# P09_DRV2605L_Motor_Driver.net
KiCad netlist of a schematic drawn in Altium Designer
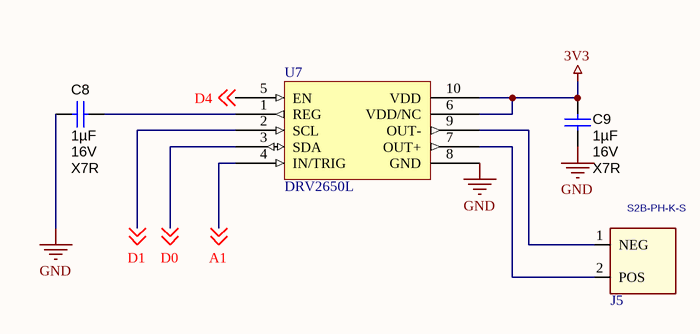
[diagram p0: P09_DRV2605L Motor Driver.SchDoc]

(export (version "E")
  (design (tool "Eeschema 10.0.6"))
  (components
    (comp (ref "C8")
      (value "C1608X7R1C105K")
      (footprint "0603")
      (description "CAP, CERM, 1 µF, 16 V, +/- 10%, X7R, 0603")
      (fields
        (field (name "MANUFACTURER") "TDK")
        (field (name "VALUEDISPLAYED") "1µF")
        (field (name "VALUE2") "16V")
        (field (name "TEMPCO") "X7R")
        (field (name "PUBLISHER") "Texas Instruments")
      )
      (libsource (lib "SLEEPTRACK2_PHASE3_Library") (part "C1608X7R1C105K"))
    )
    (comp (ref "C9")
      (value "C1608X7R1C105K")
      (footprint "0603")
      (description "CAP, CERM, 1 µF, 16 V, +/- 10%, X7R, 0603")
      (fields
        (field (name "MANUFACTURER") "TDK")
        (field (name "VALUEDISPLAYED") "1µF")
        (field (name "VALUE2") "16V")
        (field (name "TEMPCO") "X7R")
        (field (name "PUBLISHER") "Texas Instruments")
      )
      (libsource (lib "SLEEPTRACK2_PHASE3_Library") (part "C1608X7R1C105K"))
    )
    (comp (ref "J5")
      (value "S2B-PH-K-S")
      (footprint "S2B-PH-K-S")
      (description "2 Positions Header, Shrouded Connector 0.079\" (2.00mm) Through Hole, Right Angle Tin")
      (libsource (lib "SLEEPTRACK2_PHASE3_Library") (part "S2B-PH-K-S"))
    )
    (comp (ref "U7")
      (value "DRV2650L")
      (footprint "DGS0010A_N")
      (libsource (lib "SLEEPTRACK2_PHASE3_Library") (part "DRV2650L"))
    )
  )
  (nets
    (net (code "1") (name "3V3") (class "Default")
      (node (ref "C9") (pin "1") (pinfunction "1_1") (pintype "passive"))
      (node (ref "U7") (pin "10") (pinfunction "VDD_10") (pintype "power_in"))
      (node (ref "U7") (pin "6") (pinfunction "VDD/NC_6") (pintype "power_in"))
    )
    (net (code "2") (name "A1") (class "Default")
      (node (ref "U7") (pin "4") (pinfunction "IN/TRIG_4") (pintype "input"))
    )
    (net (code "3") (name "D0") (class "Default")
      (node (ref "U7") (pin "3") (pinfunction "SDA_3") (pintype "bidirectional"))
    )
    (net (code "4") (name "D1") (class "Default")
      (node (ref "U7") (pin "2") (pinfunction "SCL_2") (pintype "input"))
    )
    (net (code "5") (name "D4") (class "Default")
      (node (ref "U7") (pin "5") (pinfunction "EN_5") (pintype "input"))
    )
    (net (code "6") (name "GND") (class "Default")
      (node (ref "C8") (pin "2") (pinfunction "2_2") (pintype "passive"))
      (node (ref "C9") (pin "2") (pinfunction "2_2") (pintype "passive"))
      (node (ref "U7") (pin "8") (pinfunction "GND_8") (pintype "power_in"))
    )
    (net (code "7") (name "Net-(J5-NEG)") (class "Default")
      (node (ref "J5") (pin "1") (pinfunction "NEG_1") (pintype "passive"))
      (node (ref "U7") (pin "9") (pinfunction "OUT-_9") (pintype "output"))
    )
    (net (code "8") (name "Net-(J5-POS)") (class "Default")
      (node (ref "J5") (pin "2") (pinfunction "POS_2") (pintype "passive"))
      (node (ref "U7") (pin "7") (pinfunction "OUT+_7") (pintype "output"))
    )
    (net (code "9") (name "Net-(U7-REG)") (class "Default")
      (node (ref "C8") (pin "1") (pinfunction "1_1") (pintype "passive"))
      (node (ref "U7") (pin "1") (pinfunction "REG_1") (pintype "output"))
    )
  )
)
